# HABduino41.net
KiCad netlist of a schematic drawn in EAGLE
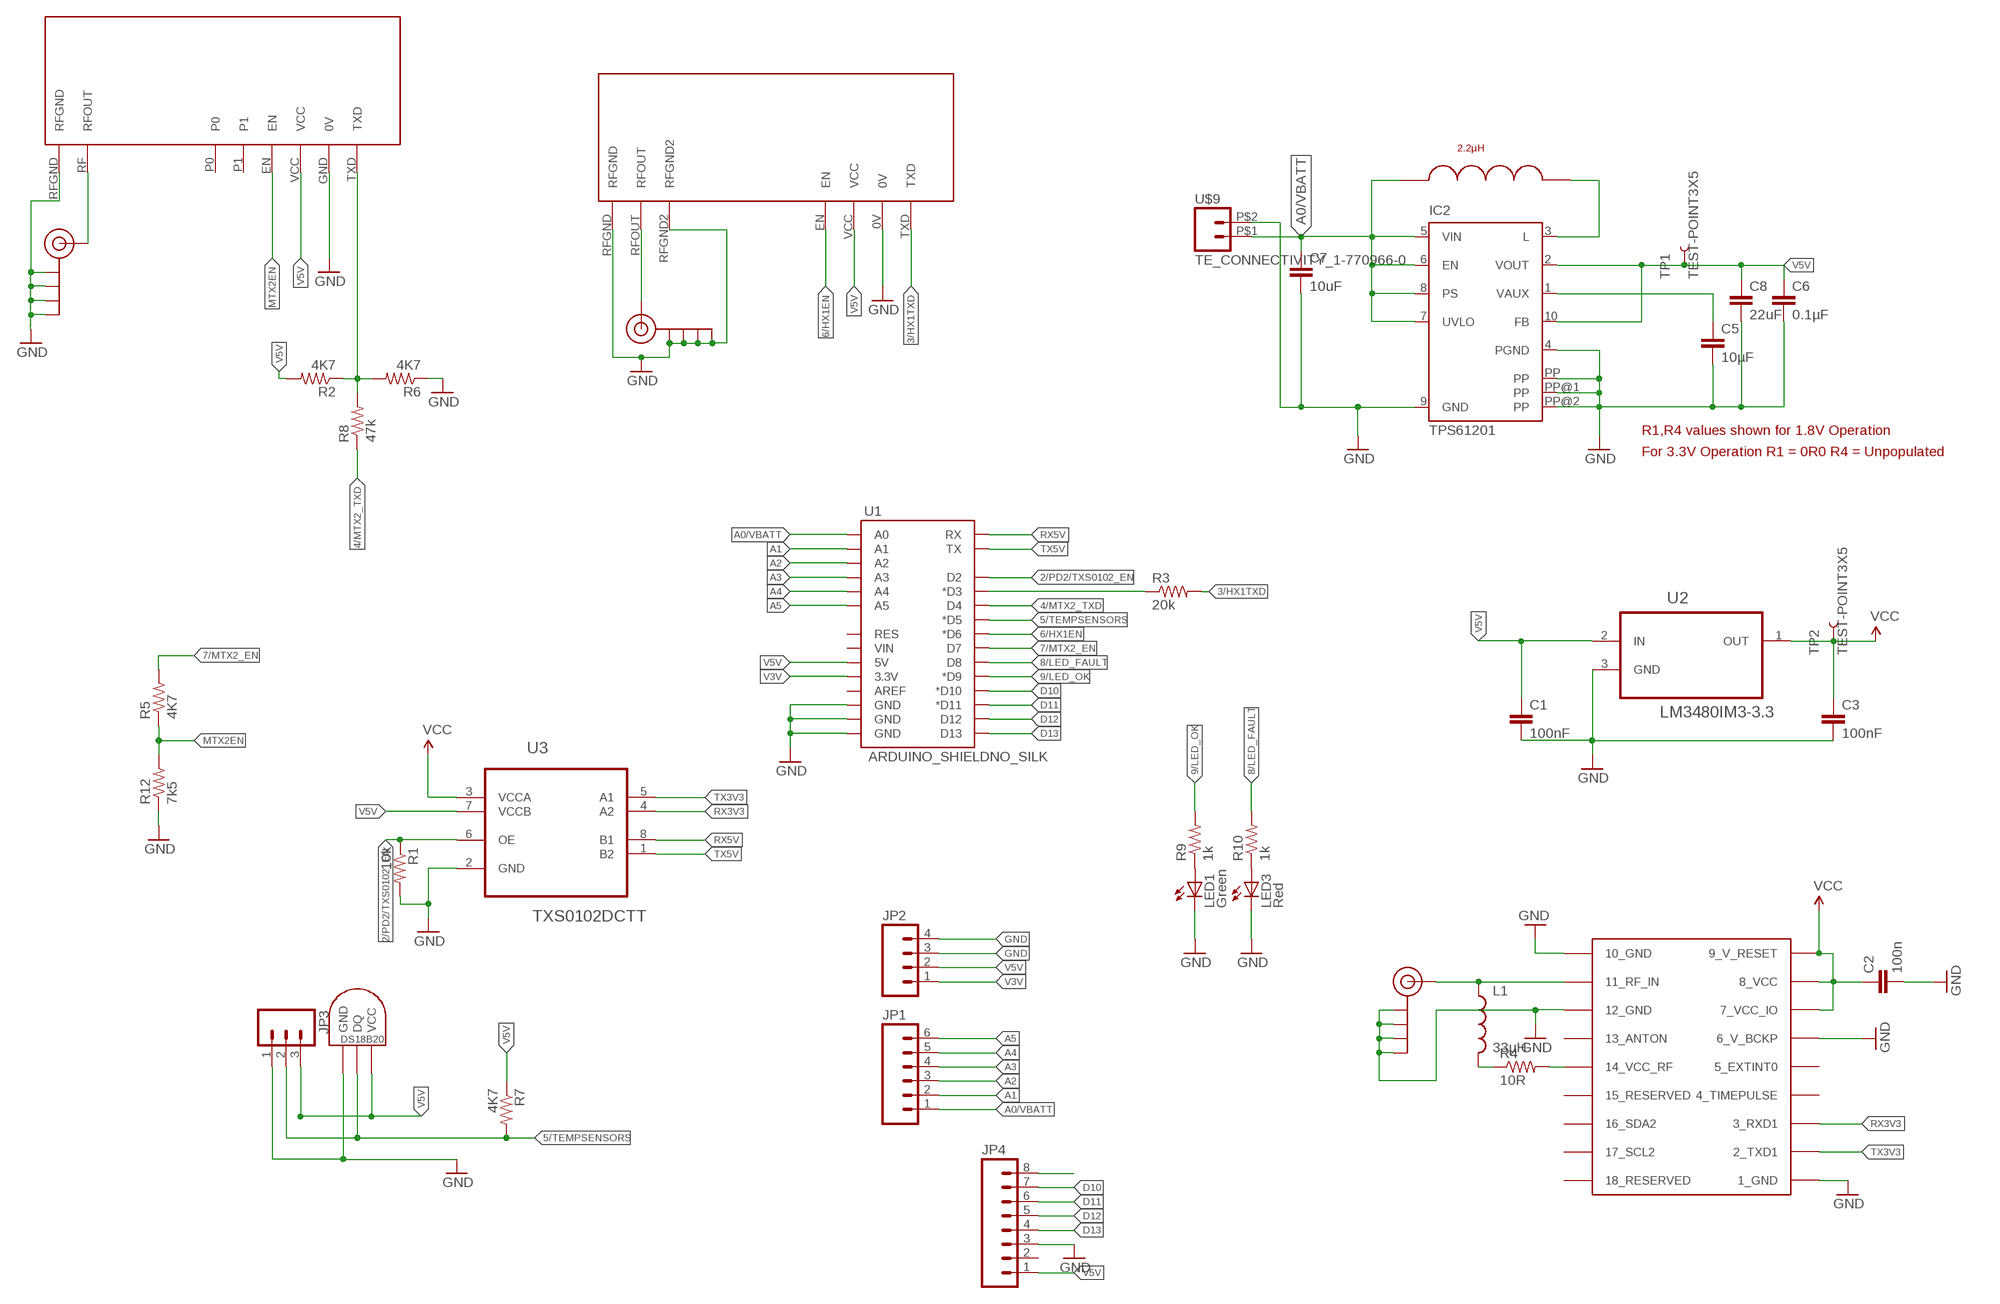
[diagram p0: schematic, sheet 1]

(export (version "E")
  (design (tool "Eeschema 10.0.6"))
  (components
    (comp (ref "C1")
      (value "100nF")
      (footprint "eagle-import:0603-CAP")
      (libsource (lib "eagle-import") (part "CAP0603-CAP"))
    )
    (comp (ref "C2")
      (value "100n")
      (footprint "eagle-import:0603-CAP")
      (libsource (lib "eagle-import") (part "CAP0603-CAP"))
    )
    (comp (ref "C3")
      (value "100nF")
      (footprint "eagle-import:0603-CAP")
      (libsource (lib "eagle-import") (part "CAP0603-CAP"))
    )
    (comp (ref "C5")
      (value "10µF")
      (footprint "eagle-import:0603-CAP")
      (libsource (lib "eagle-import") (part "CAP0603-CAP"))
    )
    (comp (ref "C6")
      (value "0.1µF")
      (footprint "eagle-import:0603-CAP")
      (libsource (lib "eagle-import") (part "CAP0603-CAP"))
    )
    (comp (ref "C7")
      (value "10uF")
      (footprint "eagle-import:1206")
      (libsource (lib "eagle-import") (part "CAP1206"))
    )
    (comp (ref "C8")
      (value "22uF")
      (footprint "eagle-import:1206")
      (libsource (lib "eagle-import") (part "CAP1206"))
    )
    (comp (ref "IC2")
      (value "TPS61201")
      (footprint "eagle-import:S-PDSO-N10")
      (fields (field (name "MPN") "TPS61201DRCT"))
      (libsource (lib "eagle-import") (part "TPS61201"))
    )
    (comp (ref "J$1")
      (value "SMA_EDGE")
      (footprint "eagle-import:SMA-EDGE")
      (libsource (lib "eagle-import") (part "SMA_EDGE"))
    )
    (comp (ref "J$2")
      (value "SMA_EDGE")
      (footprint "eagle-import:SMA-EDGE")
      (libsource (lib "eagle-import") (part "SMA_EDGE"))
    )
    (comp (ref "J$4")
      (value "SMA_EDGE")
      (footprint "eagle-import:SMA-EDGE")
      (libsource (lib "eagle-import") (part "SMA_EDGE"))
    )
    (comp (ref "JP1")
      (value "M06SIP")
      (footprint "eagle-import:1X06")
      (libsource (lib "eagle-import") (part "M06SIP"))
    )
    (comp (ref "JP2")
      (value "M04PTH")
      (footprint "eagle-import:1X04")
      (libsource (lib "eagle-import") (part "M04PTH"))
    )
    (comp (ref "JP3")
      (value "M03PTH")
      (footprint "eagle-import:1X03")
      (libsource (lib "eagle-import") (part "M03PTH"))
    )
    (comp (ref "JP4")
      (value "M081X08")
      (footprint "eagle-import:1X08")
      (libsource (lib "eagle-import") (part "M081X08"))
    )
    (comp (ref "L1")
      (value "33µH")
      (footprint "eagle-import:0603")
      (libsource (lib "eagle-import") (part "INDUCTOR0603"))
    )
    (comp (ref "LED1")
      (value "Green")
      (footprint "eagle-import:LED-0603")
      (libsource (lib "eagle-import") (part "LED0603"))
    )
    (comp (ref "LED3")
      (value "Red")
      (footprint "eagle-import:LED-0603")
      (libsource (lib "eagle-import") (part "LED0603"))
    )
    (comp (ref "LPS4018")
      (value "2.2µH")
      (footprint "eagle-import:COILCRAFT_LPS4018")
      (libsource (lib "eagle-import") (part "COILCRAFT_LPS4018"))
    )
    (comp (ref "R1")
      (value "10k")
      (footprint "eagle-import:0603-RES")
      (libsource (lib "eagle-import") (part "RESISTOR0603-RES"))
    )
    (comp (ref "R2")
      (value "4K7")
      (footprint "eagle-import:0603-RES")
      (libsource (lib "eagle-import") (part "RESISTOR0603-RES"))
    )
    (comp (ref "R3")
      (value "20k")
      (footprint "eagle-import:0603-RES")
      (libsource (lib "eagle-import") (part "RESISTOR0603-RES"))
    )
    (comp (ref "R4")
      (value "10R")
      (footprint "eagle-import:0603-RES")
      (libsource (lib "eagle-import") (part "RESISTOR0603-RES"))
    )
    (comp (ref "R5")
      (value "4K7")
      (footprint "eagle-import:0603-RES")
      (libsource (lib "eagle-import") (part "RESISTOR0603-RES"))
    )
    (comp (ref "R6")
      (value "4K7")
      (footprint "eagle-import:0603-RES")
      (libsource (lib "eagle-import") (part "RESISTOR0603-RES"))
    )
    (comp (ref "R7")
      (value "4K7")
      (footprint "eagle-import:0603-RES")
      (libsource (lib "eagle-import") (part "RESISTOR0603-RES"))
    )
    (comp (ref "R8")
      (value "47k")
      (footprint "eagle-import:0603-RES")
      (libsource (lib "eagle-import") (part "RESISTOR0603-RES"))
    )
    (comp (ref "R9")
      (value "1k")
      (footprint "eagle-import:0603-RES")
      (libsource (lib "eagle-import") (part "RESISTOR0603-RES"))
    )
    (comp (ref "R10")
      (value "1k")
      (footprint "eagle-import:0603-RES")
      (libsource (lib "eagle-import") (part "RESISTOR0603-RES"))
    )
    (comp (ref "R12")
      (value "7k5")
      (footprint "eagle-import:0603-RES")
      (libsource (lib "eagle-import") (part "RESISTOR0603-RES"))
    )
    (comp (ref "TEMP")
      (value "DS1821")
      (footprint "eagle-import:DS18B20_SOIC")
      (libsource (lib "eagle-import") (part "DS1820SOIC"))
    )
    (comp (ref "TP1")
      (value "TEST-POINT3X5")
      (footprint "eagle-import:PAD.03X.05")
      (libsource (lib "eagle-import") (part "TEST-POINT3X5"))
    )
    (comp (ref "TP2")
      (value "TEST-POINT3X5")
      (footprint "eagle-import:PAD.03X.05")
      (libsource (lib "eagle-import") (part "TEST-POINT3X5"))
    )
    (comp (ref "U$1")
      (value "UBLOX_MAX")
      (footprint "eagle-import:UBLOX_MAX")
      (libsource (lib "eagle-import") (part "UBLOX_MAX"))
    )
    (comp (ref "U$2")
      (value "RADIOMETRIX-HX1")
      (footprint "eagle-import:RADIOMETRIX-HX1")
      (libsource (lib "eagle-import") (part "RADIOMETRIX-HX1"))
    )
    (comp (ref "U$4")
      (value "RADIOMETRIX-MTX2")
      (footprint "eagle-import:RADIOMETRIX-MTX2")
      (libsource (lib "eagle-import") (part "RADIOMETRIX-MTX2"))
    )
    (comp (ref "U$9")
      (value "TE_CONNECTIVITY_1-770966-0")
      (footprint "eagle-import:TE_CONNECTIVITY_1-770966-0")
      (libsource (lib "eagle-import") (part "TE_CONNECTIVITY_1-770966-0"))
    )
    (comp (ref "U1")
      (value "ARDUINO_SHIELDNO_SILK")
      (footprint "eagle-import:DUEMILANOVE_VIAS")
      (libsource (lib "eagle-import") (part "ARDUINO_SHIELDNO_SILK"))
    )
    (comp (ref "U2")
      (value "LM3480IM3-3.3")
      (footprint "eagle-import:SOT95P251X112-3N")
      (libsource (lib "eagle-import") (part "LM3480IM3-3.3"))
    )
    (comp (ref "U3")
      (value "TXS0102DCTT")
      (footprint "eagle-import:SOP65P400X130-8N")
      (libsource (lib "eagle-import") (part "TXS0102DCTT"))
    )
  )
  (nets
    (net (code "1") (name "2{slash}PD2{slash}TXS0102_EN") (class "Default")
      (node (ref "R1") (pin "1") (pinfunction "1_1") (pintype "passive"))
      (node (ref "U1") (pin "D2") (pinfunction "D2_D2") (pintype "bidirectional"))
      (node (ref "U3") (pin "6") (pinfunction "OE_6") (pintype "input"))
    )
    (net (code "2") (name "3{slash}HX1TXD") (class "Default")
      (node (ref "R3") (pin "2") (pinfunction "2_2") (pintype "passive"))
      (node (ref "U$2") (pin "TXD") (pinfunction "TXD_TXD") (pintype "bidirectional"))
    )
    (net (code "3") (name "4{slash}MTX2_TXD") (class "Default")
      (node (ref "R8") (pin "1") (pinfunction "1_1") (pintype "passive"))
      (node (ref "U1") (pin "D4") (pinfunction "D4_D4") (pintype "bidirectional"))
    )
    (net (code "4") (name "5{slash}TEMPSENSORS") (class "Default")
      (node (ref "JP3") (pin "2") (pinfunction "2_2") (pintype "passive"))
      (node (ref "R7") (pin "2") (pinfunction "2_2") (pintype "passive"))
      (node (ref "TEMP") (pin "DQ") (pinfunction "DQ_DQ") (pintype "bidirectional"))
      (node (ref "U1") (pin "D5") (pinfunction "*D5_D5") (pintype "bidirectional"))
    )
    (net (code "5") (name "6{slash}HX1EN") (class "Default")
      (node (ref "U$2") (pin "EN") (pinfunction "EN_EN") (pintype "bidirectional"))
      (node (ref "U1") (pin "D6") (pinfunction "*D6_D6") (pintype "bidirectional"))
    )
    (net (code "6") (name "7{slash}MTX2_EN") (class "Default")
      (node (ref "R5") (pin "2") (pinfunction "2_2") (pintype "passive"))
      (node (ref "U1") (pin "D7") (pinfunction "D7_D7") (pintype "bidirectional"))
    )
    (net (code "7") (name "8{slash}LED_FAULT") (class "Default")
      (node (ref "R10") (pin "2") (pinfunction "2_2") (pintype "passive"))
      (node (ref "U1") (pin "D8") (pinfunction "D8_D8") (pintype "bidirectional"))
    )
    (net (code "8") (name "9{slash}LED_OK") (class "Default")
      (node (ref "R9") (pin "2") (pinfunction "2_2") (pintype "passive"))
      (node (ref "U1") (pin "D9") (pinfunction "*D9_D9") (pintype "bidirectional"))
    )
    (net (code "9") (name "A0{slash}VBATT") (class "Default")
      (node (ref "C7") (pin "1") (pinfunction "1_1") (pintype "passive"))
      (node (ref "IC2") (pin "5") (pinfunction "VIN_5") (pintype "input"))
      (node (ref "IC2") (pin "6") (pinfunction "EN_6") (pintype "input"))
      (node (ref "IC2") (pin "7") (pinfunction "UVLO_7") (pintype "input"))
      (node (ref "IC2") (pin "8") (pinfunction "PS_8") (pintype "input"))
      (node (ref "JP1") (pin "1") (pinfunction "1_1") (pintype "passive"))
      (node (ref "LPS4018") (pin "P$1") (pinfunction "P$1_P$1") (pintype "bidirectional"))
      (node (ref "U$9") (pin "P$1") (pinfunction "1_P$1") (pintype "passive"))
      (node (ref "U1") (pin "A0") (pinfunction "A0_A0") (pintype "bidirectional"))
    )
    (net (code "10") (name "A1") (class "Default")
      (node (ref "JP1") (pin "2") (pinfunction "2_2") (pintype "passive"))
      (node (ref "JP4") (pin "8") (pinfunction "8_8") (pintype "passive"))
      (node (ref "U1") (pin "A1") (pinfunction "A1_A1") (pintype "bidirectional"))
    )
    (net (code "11") (name "A2") (class "Default")
      (node (ref "JP1") (pin "3") (pinfunction "3_3") (pintype "passive"))
      (node (ref "U1") (pin "A2") (pinfunction "A2_A2") (pintype "bidirectional"))
    )
    (net (code "12") (name "A3") (class "Default")
      (node (ref "JP1") (pin "4") (pinfunction "4_4") (pintype "passive"))
      (node (ref "U1") (pin "A3") (pinfunction "A3_A3") (pintype "bidirectional"))
    )
    (net (code "13") (name "A4") (class "Default")
      (node (ref "JP1") (pin "5") (pinfunction "5_5") (pintype "passive"))
      (node (ref "U1") (pin "A4") (pinfunction "A4_A4") (pintype "bidirectional"))
    )
    (net (code "14") (name "A5") (class "Default")
      (node (ref "JP1") (pin "6") (pinfunction "6_6") (pintype "passive"))
      (node (ref "U1") (pin "A5") (pinfunction "A5_A5") (pintype "bidirectional"))
    )
    (net (code "15") (name "D10") (class "Default")
      (node (ref "JP4") (pin "7") (pinfunction "7_7") (pintype "passive"))
      (node (ref "U1") (pin "D10") (pinfunction "*D10_D10") (pintype "bidirectional"))
    )
    (net (code "16") (name "D11") (class "Default")
      (node (ref "JP4") (pin "6") (pinfunction "6_6") (pintype "passive"))
      (node (ref "U1") (pin "D11") (pinfunction "*D11_D11") (pintype "bidirectional"))
    )
    (net (code "17") (name "D12") (class "Default")
      (node (ref "JP4") (pin "5") (pinfunction "5_5") (pintype "passive"))
      (node (ref "U1") (pin "D12") (pinfunction "D12_D12") (pintype "bidirectional"))
    )
    (net (code "18") (name "D13") (class "Default")
      (node (ref "JP4") (pin "4") (pinfunction "4_4") (pintype "passive"))
      (node (ref "U1") (pin "D13") (pinfunction "D13_D13") (pintype "bidirectional"))
    )
    (net (code "19") (name "GND") (class "Default")
      (node (ref "C1") (pin "2") (pinfunction "2_2") (pintype "passive"))
      (node (ref "C2") (pin "2") (pinfunction "2_2") (pintype "passive"))
      (node (ref "C3") (pin "2") (pinfunction "2_2") (pintype "passive"))
      (node (ref "C5") (pin "2") (pinfunction "2_2") (pintype "passive"))
      (node (ref "C6") (pin "2") (pinfunction "2_2") (pintype "passive"))
      (node (ref "C7") (pin "2") (pinfunction "2_2") (pintype "passive"))
      (node (ref "C8") (pin "2") (pinfunction "2_2") (pintype "passive"))
      (node (ref "IC2") (pin "4") (pinfunction "PGND_4") (pintype "power_in"))
      (node (ref "IC2") (pin "9") (pinfunction "GND_9") (pintype "power_in"))
      (node (ref "IC2") (pin "PP") (pinfunction "PP_PP") (pintype "power_in"))
      (node (ref "IC2") (pin "PP@1") (pinfunction "PP_PP@1") (pintype "power_in"))
      (node (ref "IC2") (pin "PP@2") (pinfunction "PP_PP@2") (pintype "power_in"))
      (node (ref "J$1") (pin "GND@0") (pinfunction "GND_GND@0") (pintype "bidirectional"))
      (node (ref "J$1") (pin "GND@1") (pinfunction "GND_GND@1") (pintype "bidirectional"))
      (node (ref "J$1") (pin "GND@2") (pinfunction "GND_GND@2") (pintype "bidirectional"))
      (node (ref "J$1") (pin "GND@3") (pinfunction "GND_GND@3") (pintype "bidirectional"))
      (node (ref "J$2") (pin "GND@0") (pinfunction "GND_GND@0") (pintype "bidirectional"))
      (node (ref "J$2") (pin "GND@1") (pinfunction "GND_GND@1") (pintype "bidirectional"))
      (node (ref "J$2") (pin "GND@2") (pinfunction "GND_GND@2") (pintype "bidirectional"))
      (node (ref "J$2") (pin "GND@3") (pinfunction "GND_GND@3") (pintype "bidirectional"))
      (node (ref "J$4") (pin "GND@0") (pinfunction "GND_GND@0") (pintype "bidirectional"))
      (node (ref "J$4") (pin "GND@1") (pinfunction "GND_GND@1") (pintype "bidirectional"))
      (node (ref "J$4") (pin "GND@2") (pinfunction "GND_GND@2") (pintype "bidirectional"))
      (node (ref "J$4") (pin "GND@3") (pinfunction "GND_GND@3") (pintype "bidirectional"))
      (node (ref "JP2") (pin "3") (pinfunction "3_3") (pintype "passive"))
      (node (ref "JP2") (pin "4") (pinfunction "4_4") (pintype "passive"))
      (node (ref "JP3") (pin "1") (pinfunction "1_1") (pintype "passive"))
      (node (ref "JP4") (pin "3") (pinfunction "3_3") (pintype "passive"))
      (node (ref "LED1") (pin "C") (pinfunction "C_C") (pintype "passive"))
      (node (ref "LED3") (pin "C") (pinfunction "C_C") (pintype "passive"))
      (node (ref "R1") (pin "2") (pinfunction "2_2") (pintype "passive"))
      (node (ref "R12") (pin "1") (pinfunction "1_1") (pintype "passive"))
      (node (ref "R6") (pin "1") (pinfunction "1_1") (pintype "passive"))
      (node (ref "TEMP") (pin "GND") (pinfunction "GND_GND") (pintype "power_in"))
      (node (ref "U$1") (pin "10_GND") (pinfunction "10_GND_10_GND") (pintype "power_in"))
      (node (ref "U$1") (pin "12_GND") (pinfunction "12_GND_12_GND") (pintype "power_in"))
      (node (ref "U$1") (pin "1_GND") (pinfunction "1_GND_1_GND") (pintype "power_in"))
      (node (ref "U$1") (pin "6_V_BCKP") (pinfunction "6_V_BCKP_6_V_BCKP") (pintype "bidirectional"))
      (node (ref "U$2") (pin "0V") (pinfunction "0V_0V") (pintype "bidirectional"))
      (node (ref "U$2") (pin "RFGND") (pinfunction "RFGND_RFGND") (pintype "bidirectional"))
      (node (ref "U$2") (pin "RFGND2") (pinfunction "RFGND2_RFGND2") (pintype "bidirectional"))
      (node (ref "U$4") (pin "GND") (pinfunction "0V_GND") (pintype "bidirectional"))
      (node (ref "U$4") (pin "RFGND") (pinfunction "RFGND_RFGND") (pintype "bidirectional"))
      (node (ref "U$9") (pin "P$2") (pinfunction "2_P$2") (pintype "passive"))
      (node (ref "U1") (pin "GND@0") (pinfunction "GND_GND@0") (pintype "bidirectional"))
      (node (ref "U1") (pin "GND@1") (pinfunction "GND_GND@1") (pintype "bidirectional"))
      (node (ref "U1") (pin "GND@2") (pinfunction "GND_GND@2") (pintype "bidirectional"))
      (node (ref "U2") (pin "3") (pinfunction "GND_3") (pintype "passive"))
      (node (ref "U3") (pin "2") (pinfunction "GND_2") (pintype "passive"))
    )
    (net (code "20") (name "MTX2EN") (class "Default")
      (node (ref "R12") (pin "2") (pinfunction "2_2") (pintype "passive"))
      (node (ref "R5") (pin "1") (pinfunction "1_1") (pintype "passive"))
      (node (ref "U$4") (pin "EN") (pinfunction "EN_EN") (pintype "bidirectional"))
    )
    (net (code "21") (name "Net-(IC2-L)") (class "Default")
      (node (ref "IC2") (pin "3") (pinfunction "L_3") (pintype "input"))
      (node (ref "LPS4018") (pin "P$2") (pinfunction "P$2_P$2") (pintype "bidirectional"))
    )
    (net (code "22") (name "Net-(IC2-VAUX)") (class "Default")
      (node (ref "C5") (pin "1") (pinfunction "1_1") (pintype "passive"))
      (node (ref "IC2") (pin "1") (pinfunction "VAUX_1") (pintype "bidirectional"))
    )
    (net (code "23") (name "Net-(J$1-SIGNAL)") (class "Default")
      (node (ref "J$1") (pin "SIG") (pinfunction "SIGNAL_SIG") (pintype "bidirectional"))
      (node (ref "U$4") (pin "RF") (pinfunction "RFOUT_RF") (pintype "bidirectional"))
    )
    (net (code "24") (name "Net-(J$2-SIGNAL)") (class "Default")
      (node (ref "J$2") (pin "SIG") (pinfunction "SIGNAL_SIG") (pintype "bidirectional"))
      (node (ref "L1") (pin "1") (pinfunction "1_1") (pintype "passive"))
      (node (ref "U$1") (pin "11_RF_IN") (pinfunction "11_RF_IN_11_RF_IN") (pintype "bidirectional"))
    )
    (net (code "25") (name "Net-(J$4-SIGNAL)") (class "Default")
      (node (ref "J$4") (pin "SIG") (pinfunction "SIGNAL_SIG") (pintype "bidirectional"))
      (node (ref "U$2") (pin "RFOUT") (pinfunction "RFOUT_RFOUT") (pintype "bidirectional"))
    )
    (net (code "26") (name "Net-(L1-Pad2)") (class "Default")
      (node (ref "L1") (pin "2") (pinfunction "2_2") (pintype "passive"))
      (node (ref "R4") (pin "1") (pinfunction "1_1") (pintype "passive"))
    )
    (net (code "27") (name "Net-(LED1-PadA)") (class "Default")
      (node (ref "LED1") (pin "A") (pinfunction "A_A") (pintype "passive"))
      (node (ref "R9") (pin "1") (pinfunction "1_1") (pintype "passive"))
    )
    (net (code "28") (name "Net-(LED3-PadA)") (class "Default")
      (node (ref "LED3") (pin "A") (pinfunction "A_A") (pintype "passive"))
      (node (ref "R10") (pin "1") (pinfunction "1_1") (pintype "passive"))
    )
    (net (code "29") (name "Net-(R2-Pad1)") (class "Default")
      (node (ref "R2") (pin "1") (pinfunction "1_1") (pintype "passive"))
      (node (ref "R6") (pin "2") (pinfunction "2_2") (pintype "passive"))
      (node (ref "R8") (pin "2") (pinfunction "2_2") (pintype "passive"))
      (node (ref "U$4") (pin "TXD") (pinfunction "TXD_TXD") (pintype "bidirectional"))
    )
    (net (code "30") (name "Net-(R4-Pad2)") (class "Default")
      (node (ref "R4") (pin "2") (pinfunction "2_2") (pintype "passive"))
      (node (ref "U$1") (pin "14_VCC_RF") (pinfunction "14_VCC_RF_14_VCC_RF") (pintype "bidirectional"))
    )
    (net (code "31") (name "Net-(U1-*D3)") (class "Default")
      (node (ref "R3") (pin "1") (pinfunction "1_1") (pintype "passive"))
      (node (ref "U1") (pin "D3") (pinfunction "*D3_D3") (pintype "bidirectional"))
    )
    (net (code "32") (name "RX3V3") (class "Default")
      (node (ref "U$1") (pin "3_RXD1") (pinfunction "3_RXD1_3_RXD1") (pintype "bidirectional"))
      (node (ref "U3") (pin "4") (pinfunction "A2_4") (pintype "bidirectional"))
    )
    (net (code "33") (name "RX5V") (class "Default")
      (node (ref "U1") (pin "RX") (pinfunction "RX_RX") (pintype "bidirectional"))
      (node (ref "U3") (pin "8") (pinfunction "B1_8") (pintype "bidirectional"))
    )
    (net (code "34") (name "TX3V3") (class "Default")
      (node (ref "U$1") (pin "2_TXD1") (pinfunction "2_TXD1_2_TXD1") (pintype "bidirectional"))
      (node (ref "U3") (pin "5") (pinfunction "A1_5") (pintype "bidirectional"))
    )
    (net (code "35") (name "TX5V") (class "Default")
      (node (ref "U1") (pin "TX") (pinfunction "TX_TX") (pintype "bidirectional"))
      (node (ref "U3") (pin "1") (pinfunction "B2_1") (pintype "bidirectional"))
    )
    (net (code "36") (name "V3V") (class "Default")
      (node (ref "JP2") (pin "1") (pinfunction "1_1") (pintype "passive"))
      (node (ref "U1") (pin "3.3V") (pinfunction "3.3V_3.3V") (pintype "bidirectional"))
    )
    (net (code "37") (name "V5V") (class "Default")
      (node (ref "C1") (pin "1") (pinfunction "1_1") (pintype "passive"))
      (node (ref "C6") (pin "1") (pinfunction "1_1") (pintype "passive"))
      (node (ref "C8") (pin "1") (pinfunction "1_1") (pintype "passive"))
      (node (ref "IC2") (pin "10") (pinfunction "FB_10") (pintype "input"))
      (node (ref "IC2") (pin "2") (pinfunction "VOUT_2") (pintype "passive"))
      (node (ref "JP2") (pin "2") (pinfunction "2_2") (pintype "passive"))
      (node (ref "JP3") (pin "3") (pinfunction "3_3") (pintype "passive"))
      (node (ref "JP4") (pin "1") (pinfunction "1_1") (pintype "passive"))
      (node (ref "R2") (pin "2") (pinfunction "2_2") (pintype "passive"))
      (node (ref "R7") (pin "1") (pinfunction "1_1") (pintype "passive"))
      (node (ref "TEMP") (pin "VCC") (pinfunction "VCC_VCC") (pintype "power_in"))
      (node (ref "TP1") (pin "P$1") (pinfunction "1_P$1") (pintype "bidirectional"))
      (node (ref "U$2") (pin "VCC") (pinfunction "VCC_VCC") (pintype "bidirectional"))
      (node (ref "U$4") (pin "VCC") (pinfunction "VCC_VCC") (pintype "bidirectional"))
      (node (ref "U1") (pin "5V") (pinfunction "5V_5V") (pintype "bidirectional"))
      (node (ref "U2") (pin "2") (pinfunction "IN_2") (pintype "power_in"))
      (node (ref "U3") (pin "7") (pinfunction "VCCB_7") (pintype "power_in"))
    )
    (net (code "38") (name "VCC") (class "Default")
      (node (ref "C2") (pin "1") (pinfunction "1_1") (pintype "passive"))
      (node (ref "C3") (pin "1") (pinfunction "1_1") (pintype "passive"))
      (node (ref "TP2") (pin "P$1") (pinfunction "1_P$1") (pintype "bidirectional"))
      (node (ref "U$1") (pin "7_VCC_IO") (pinfunction "7_VCC_IO_7_VCC_IO") (pintype "power_in"))
      (node (ref "U$1") (pin "8_VCC") (pinfunction "8_VCC_8_VCC") (pintype "power_in"))
      (node (ref "U$1") (pin "9_V_RESET") (pinfunction "9_V_RESET_9_V_RESET") (pintype "power_in"))
      (node (ref "U2") (pin "1") (pinfunction "OUT_1") (pintype "output"))
      (node (ref "U3") (pin "3") (pinfunction "VCCA_3") (pintype "power_in"))
    )
    (net (code "39") (name "unconnected-(JP4-Pad2)") (class "Default")
      (node (ref "JP4") (pin "2") (pinfunction "2_2") (pintype "passive"))
    )
    (net (code "40") (name "unconnected-(U$1-Pad4_TIMEPULSE)") (class "Default")
      (node (ref "U$1") (pin "4_TIMEPULSE") (pinfunction "4_TIMEPULSE_4_TIMEPULSE") (pintype "bidirectional"))
    )
    (net (code "41") (name "unconnected-(U$1-Pad5_EXTINT0)") (class "Default")
      (node (ref "U$1") (pin "5_EXTINT0") (pinfunction "5_EXTINT0_5_EXTINT0") (pintype "bidirectional"))
    )
    (net (code "42") (name "unconnected-(U$1-Pad13_ANTON)") (class "Default")
      (node (ref "U$1") (pin "13_ANTON") (pinfunction "13_ANTON_13_ANTON") (pintype "bidirectional"))
    )
    (net (code "43") (name "unconnected-(U$1-Pad15_RESERVED)") (class "Default")
      (node (ref "U$1") (pin "15_RESERVED") (pinfunction "15_RESERVED_15_RESERVED") (pintype "bidirectional"))
    )
    (net (code "44") (name "unconnected-(U$1-Pad16_SDA2)") (class "Default")
      (node (ref "U$1") (pin "16_SDA2") (pinfunction "16_SDA2_16_SDA2") (pintype "bidirectional"))
    )
    (net (code "45") (name "unconnected-(U$1-Pad17_SCL2)") (class "Default")
      (node (ref "U$1") (pin "17_SCL2") (pinfunction "17_SCL2_17_SCL2") (pintype "bidirectional"))
    )
    (net (code "46") (name "unconnected-(U$1-Pad18_RESERVED)") (class "Default")
      (node (ref "U$1") (pin "18_RESERVED") (pinfunction "18_RESERVED_18_RESERVED") (pintype "bidirectional"))
    )
    (net (code "47") (name "unconnected-(U$4-PadP0)") (class "Default")
      (node (ref "U$4") (pin "P0") (pinfunction "P0_P0") (pintype "bidirectional"))
    )
    (net (code "48") (name "unconnected-(U$4-PadP1)") (class "Default")
      (node (ref "U$4") (pin "P1") (pinfunction "P1_P1") (pintype "bidirectional"))
    )
    (net (code "49") (name "unconnected-(U1-PadAREF)") (class "Default")
      (node (ref "U1") (pin "AREF") (pinfunction "AREF_AREF") (pintype "bidirectional"))
    )
    (net (code "50") (name "unconnected-(U1-PadRES)") (class "Default")
      (node (ref "U1") (pin "RES") (pinfunction "RES_RES") (pintype "bidirectional"))
    )
    (net (code "51") (name "unconnected-(U1-PadVIN)") (class "Default")
      (node (ref "U1") (pin "VIN") (pinfunction "VIN_VIN") (pintype "bidirectional"))
    )
  )
)
